# M_L_ext_switch.net
KiCad netlist of a schematic drawn in EAGLE
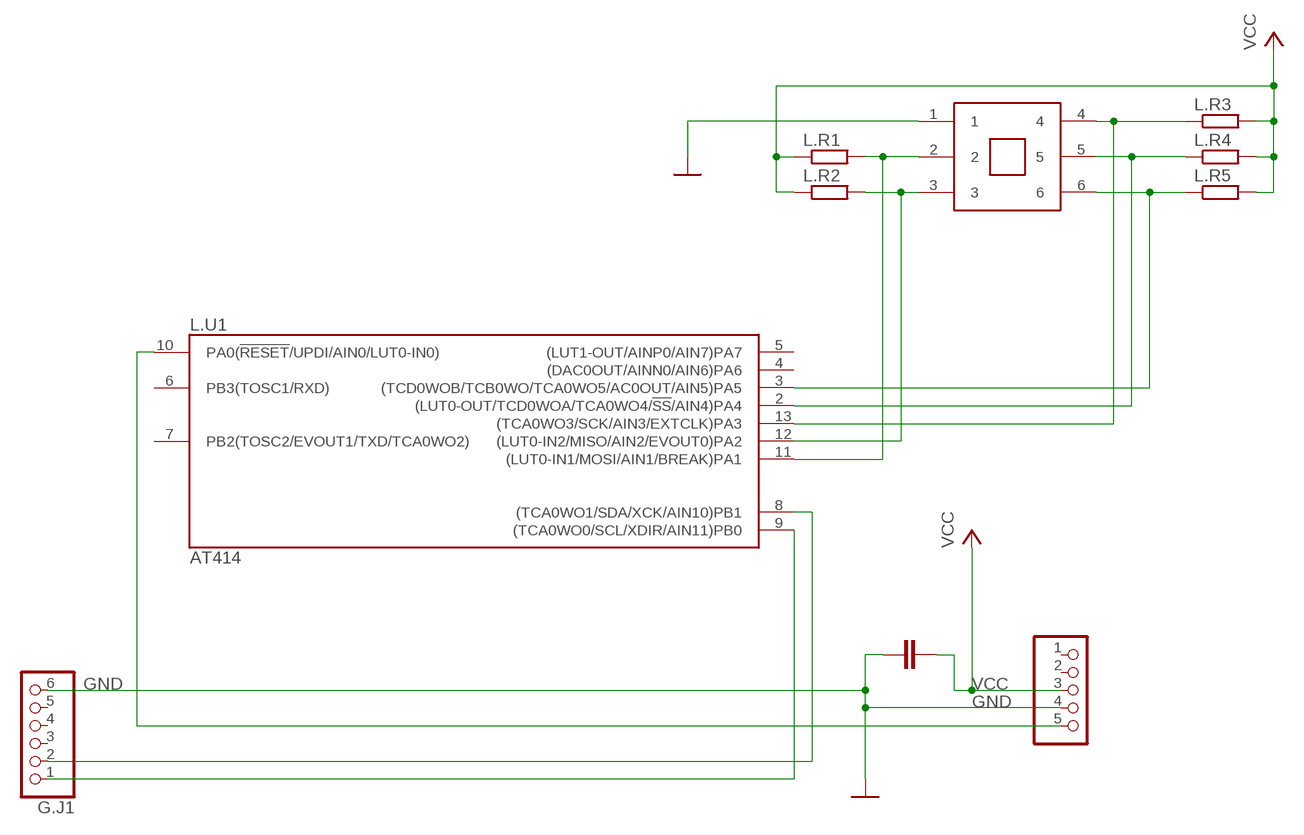
[diagram p0: schematic, sheet 1]

(export (version "E")
  (design (tool "Eeschema 10.0.6"))
  (components
    (comp (ref "G.J1")
      (value "PINHD-1X6")
      (footprint "eagle-import:1X06")
      (libsource (lib "eagle-import") (part "PINHD-1X6"))
    )
    (comp (ref "G.J2")
      (value "PINHD-1X5")
      (footprint "eagle-import:1X05")
      (libsource (lib "eagle-import") (part "PINHD-1X5"))
    )
    (comp (ref "L.C1")
      (value "100n")
      (footprint "eagle-import:C0603")
      (libsource (lib "eagle-import") (part "C-EUC0603"))
    )
    (comp (ref "L.R1")
      (value "R-EU_R0603")
      (footprint "eagle-import:R0603")
      (libsource (lib "eagle-import") (part "R-EU_R0603"))
    )
    (comp (ref "L.R2")
      (value "R-EU_R0603")
      (footprint "eagle-import:R0603")
      (libsource (lib "eagle-import") (part "R-EU_R0603"))
    )
    (comp (ref "L.R3")
      (value "R-EU_R0603")
      (footprint "eagle-import:R0603")
      (libsource (lib "eagle-import") (part "R-EU_R0603"))
    )
    (comp (ref "L.R4")
      (value "R-EU_R0603")
      (footprint "eagle-import:R0603")
      (libsource (lib "eagle-import") (part "R-EU_R0603"))
    )
    (comp (ref "L.R5")
      (value "R-EU_R0603")
      (footprint "eagle-import:R0603")
      (libsource (lib "eagle-import") (part "R-EU_R0603"))
    )
    (comp (ref "L.SW1")
      (value "5_WAY_SWITCH")
      (footprint "eagle-import:5_WAY_SWITCH")
      (libsource (lib "eagle-import") (part "5_WAY_SWITCH"))
    )
    (comp (ref "L.U1")
      (value "AT414")
      (footprint "eagle-import:SO14")
      (libsource (lib "eagle-import") (part "ATTINY14-SSF2"))
    )
  )
  (nets
    (net (code "1") (name "GND") (class "Default")
      (node (ref "G.J1") (pin "6") (pinfunction "6_6") (pintype "passive"))
      (node (ref "G.J2") (pin "4") (pinfunction "4_4") (pintype "passive"))
      (node (ref "L.C1") (pin "1") (pinfunction "1_1") (pintype "passive"))
      (node (ref "L.SW1") (pin "1") (pinfunction "1_1") (pintype "bidirectional"))
    )
    (net (code "2") (name "Net-(L.U1A-(LUT0-IN1{slash}MOSI{slash}AIN1{slash}BREAK)PA1)") (class "Default")
      (node (ref "L.R1") (pin "2") (pinfunction "2_2") (pintype "passive"))
      (node (ref "L.SW1") (pin "2") (pinfunction "2_2") (pintype "bidirectional"))
      (node (ref "L.U1") (pin "11") (pinfunction "(LUT0-IN1/MOSI/AIN1/BREAK)PA1_11") (pintype "bidirectional"))
    )
    (net (code "3") (name "Net-(L.U1A-(LUT0-IN2{slash}MISO{slash}AIN2{slash}EVOUT0)PA2)") (class "Default")
      (node (ref "L.R2") (pin "2") (pinfunction "2_2") (pintype "passive"))
      (node (ref "L.SW1") (pin "3") (pinfunction "3_3") (pintype "bidirectional"))
      (node (ref "L.U1") (pin "12") (pinfunction "(LUT0-IN2/MISO/AIN2/EVOUT0)PA2_12") (pintype "bidirectional"))
    )
    (net (code "4") (name "Net-(L.U1A-(LUT0-OUT{slash}TCD0WOA{slash}TCA0WO4{slash}~{SS}{slash}AIN4)PA4)") (class "Default")
      (node (ref "L.R4") (pin "1") (pinfunction "1_1") (pintype "passive"))
      (node (ref "L.SW1") (pin "5") (pinfunction "5_5") (pintype "bidirectional"))
      (node (ref "L.U1") (pin "2") (pinfunction "(LUT0-OUT/TCD0WOA/TCA0WO4/~{SS}/AIN4)PA4_2") (pintype "bidirectional"))
    )
    (net (code "5") (name "Net-(L.U1A-(TCA0WO0{slash}SCL{slash}XDIR{slash}AIN11)PB0)") (class "Default")
      (node (ref "G.J1") (pin "1") (pinfunction "1_1") (pintype "passive"))
      (node (ref "L.U1") (pin "9") (pinfunction "(TCA0WO0/SCL/XDIR/AIN11)PB0_9") (pintype "bidirectional"))
    )
    (net (code "6") (name "Net-(L.U1A-(TCA0WO1{slash}SDA{slash}XCK{slash}AIN10)PB1)") (class "Default")
      (node (ref "G.J1") (pin "2") (pinfunction "2_2") (pintype "passive"))
      (node (ref "L.U1") (pin "8") (pinfunction "(TCA0WO1/SDA/XCK/AIN10)PB1_8") (pintype "bidirectional"))
    )
    (net (code "7") (name "Net-(L.U1A-(TCA0WO3{slash}SCK{slash}AIN3{slash}EXTCLK)PA3)") (class "Default")
      (node (ref "L.R3") (pin "1") (pinfunction "1_1") (pintype "passive"))
      (node (ref "L.SW1") (pin "4") (pinfunction "4_4") (pintype "bidirectional"))
      (node (ref "L.U1") (pin "13") (pinfunction "(TCA0WO3/SCK/AIN3/EXTCLK)PA3_13") (pintype "bidirectional"))
    )
    (net (code "8") (name "Net-(L.U1A-(TCD0WOB{slash}TCB0WO{slash}TCA0WO5{slash}AC0OUT{slash}AIN5)PA5)") (class "Default")
      (node (ref "L.R5") (pin "1") (pinfunction "1_1") (pintype "passive"))
      (node (ref "L.SW1") (pin "6") (pinfunction "6_6") (pintype "bidirectional"))
      (node (ref "L.U1") (pin "3") (pinfunction "(TCD0WOB/TCB0WO/TCA0WO5/AC0OUT/AIN5)PA5_3") (pintype "bidirectional"))
    )
    (net (code "9") (name "Net-(L.U1A-PA0(~{RESET}{slash}UPDI{slash}AIN0{slash}LUT0-IN0))") (class "Default")
      (node (ref "G.J2") (pin "5") (pinfunction "5_5") (pintype "passive"))
      (node (ref "L.U1") (pin "10") (pinfunction "PA0(~{RESET}/UPDI/AIN0/LUT0-IN0)_10") (pintype "bidirectional"))
    )
    (net (code "10") (name "VCC") (class "Default")
      (node (ref "G.J2") (pin "3") (pinfunction "3_3") (pintype "passive"))
      (node (ref "L.C1") (pin "2") (pinfunction "2_2") (pintype "passive"))
      (node (ref "L.R1") (pin "1") (pinfunction "1_1") (pintype "passive"))
      (node (ref "L.R2") (pin "1") (pinfunction "1_1") (pintype "passive"))
      (node (ref "L.R3") (pin "2") (pinfunction "2_2") (pintype "passive"))
      (node (ref "L.R4") (pin "2") (pinfunction "2_2") (pintype "passive"))
      (node (ref "L.R5") (pin "2") (pinfunction "2_2") (pintype "passive"))
    )
    (net (code "11") (name "unconnected-(G.J1-Pad3)") (class "Default")
      (node (ref "G.J1") (pin "3") (pinfunction "3_3") (pintype "passive"))
    )
    (net (code "12") (name "unconnected-(G.J1-Pad4)") (class "Default")
      (node (ref "G.J1") (pin "4") (pinfunction "4_4") (pintype "passive"))
    )
    (net (code "13") (name "unconnected-(G.J1-Pad5)") (class "Default")
      (node (ref "G.J1") (pin "5") (pinfunction "5_5") (pintype "passive"))
    )
    (net (code "14") (name "unconnected-(G.J2-Pad1)") (class "Default")
      (node (ref "G.J2") (pin "1") (pinfunction "1_1") (pintype "passive"))
    )
    (net (code "15") (name "unconnected-(G.J2-Pad2)") (class "Default")
      (node (ref "G.J2") (pin "2") (pinfunction "2_2") (pintype "passive"))
    )
    (net (code "16") (name "unconnected-(L.U1A-(DAC0OUT{slash}AINN0{slash}AIN6)PA6-Pad4)") (class "Default")
      (node (ref "L.U1") (pin "4") (pinfunction "(DAC0OUT/AINN0/AIN6)PA6_4") (pintype "bidirectional"))
    )
    (net (code "17") (name "unconnected-(L.U1A-(LUT1-OUT{slash}AINP0{slash}AIN7)PA7-Pad5)") (class "Default")
      (node (ref "L.U1") (pin "5") (pinfunction "(LUT1-OUT/AINP0/AIN7)PA7_5") (pintype "bidirectional"))
    )
    (net (code "18") (name "unconnected-(L.U1A-PB2(TOSC2{slash}EVOUT1{slash}TXD{slash}TCA0WO2)-Pad7)") (class "Default")
      (node (ref "L.U1") (pin "7") (pinfunction "PB2(TOSC2/EVOUT1/TXD/TCA0WO2)_7") (pintype "bidirectional"))
    )
    (net (code "19") (name "unconnected-(L.U1A-PB3(TOSC1{slash}RXD)-Pad6)") (class "Default")
      (node (ref "L.U1") (pin "6") (pinfunction "PB3(TOSC1/RXD)_6") (pintype "bidirectional"))
    )
  )
)
